# MEMORY.net
KiCad netlist of a schematic drawn in Altium Designer
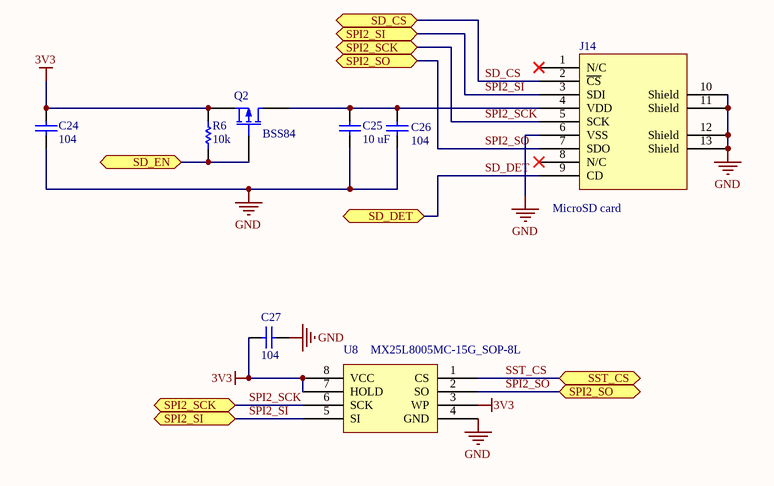
[diagram p0: MEMORY.SchDoc]

(export (version "E")
  (design (tool "Eeschema 10.0.6"))
  (components
    (comp (ref "C24")
      (value "104")
      (footprint "C0603")
      (description "CAP CER 0.1UF 16V Y5V 0402")
      (fields
        (field (name "MANUFACTURER") "Yageo")
        (field (name "DIGI-KEY PART NUMBER") "311-1047-1-ND")
        (field (name "PUBLISHER") "Altium Limited")
      )
      (libsource (lib "RobotClub") (part "Cap_SMT"))
    )
    (comp (ref "C25")
      (value "10 uF")
      (footprint "C1210")
      (description "CAP CER 0.1UF 16V Y5V 0402")
      (fields
        (field (name "MANUFACTURER") "Yageo")
        (field (name "DIGI-KEY PART NUMBER") "311-1047-1-ND")
        (field (name "PUBLISHER") "Altium Limited")
      )
      (libsource (lib "RobotClub") (part "Cap_SMT"))
    )
    (comp (ref "C26")
      (value "104")
      (footprint "C0603")
      (description "CAP CER 0.1UF 16V Y5V 0402")
      (fields
        (field (name "MANUFACTURER") "Yageo")
        (field (name "DIGI-KEY PART NUMBER") "311-1047-1-ND")
        (field (name "PUBLISHER") "Altium Limited")
      )
      (libsource (lib "RobotClub") (part "Cap_SMT"))
    )
    (comp (ref "C27")
      (value "104")
      (footprint "C0603")
      (description "CAP CER 0.1UF 16V Y5V 0402")
      (fields
        (field (name "MANUFACTURER") "Yageo")
        (field (name "DIGI-KEY PART NUMBER") "311-1047-1-ND")
        (field (name "PUBLISHER") "Altium Limited")
      )
      (libsource (lib "RobotClub") (part "Cap_SMT"))
    )
    (comp (ref "J14")
      (value "MicroSD card")
      (footprint "MICROSD SOCKET CPSDBT5")
      (fields (field (name "DIGI-KEY PART NUMBER") "NA"))
      (libsource (lib "uSD push-push socket") (part "uSD Push-Push Socket"))
    )
    (comp (ref "Q2")
      (value "BSS84")
      (footprint "SOT23-3")
      (description "MOSFET P-CH 50V 130MA SOT23-3")
      (fields
        (field (name "DIGI-KEY PART NUMBER") "BSS84-FDITR-ND")
        (field (name "MANUFACTURER") "Diodes Inc")
        (field (name "PUBLISHER") "Altium Limited")
      )
      (libsource (lib "RobotClub") (part "MOSFET-P GSD"))
    )
    (comp (ref "R6")
      (value "10k")
      (footprint "R0603")
      (description "Resistor SMD 5%")
      (fields
        (field (name "DIGI-KEY PART NUMBER") "P3.24KLTR-ND")
        (field (name "MANUFACTURER") "Panasonic Electronic Components")
        (field (name "PUBLISHER") "Altium Limited")
      )
      (libsource (lib "RobotClub") (part "R_SMD5"))
    )
    (comp (ref "U8")
      (value "MX25L8005MC-15G_SOP-8L")
      (footprint "FLASH_IC")
      (fields (field (name "DIGI-KEY PART NUMBER") "1092-1106-ND"))
      (libsource (lib "GT402Dlib") (part "MX25L8005MC-15G_SOP-8L"))
    )
  )
  (nets
    (net (code "1") (name "/SD_CS") (class "Default")
      (node (ref "J14") (pin "2") (pinfunction "~{CS}_2") (pintype "passive"))
    )
    (net (code "2") (name "/SD_DET") (class "Default")
      (node (ref "J14") (pin "9") (pinfunction "CD_9") (pintype "passive"))
    )
    (net (code "3") (name "/SD_EN") (class "Default")
      (node (ref "Q2") (pin "1") (pinfunction "G_1") (pintype "passive"))
      (node (ref "R6") (pin "2") (pinfunction "2_2") (pintype "passive"))
    )
    (net (code "4") (name "/SPI2_SCK") (class "Default")
      (node (ref "J14") (pin "5") (pinfunction "SCK_5") (pintype "passive"))
      (node (ref "U8") (pin "6") (pinfunction "SCK_6") (pintype "passive"))
    )
    (net (code "5") (name "/SPI2_SI") (class "Default")
      (node (ref "J14") (pin "3") (pinfunction "SDI_3") (pintype "passive"))
      (node (ref "U8") (pin "5") (pinfunction "SI_5") (pintype "passive"))
    )
    (net (code "6") (name "/SPI2_SO") (class "Default")
      (node (ref "J14") (pin "7") (pinfunction "SDO_7") (pintype "passive"))
      (node (ref "U8") (pin "2") (pinfunction "SO_2") (pintype "passive"))
    )
    (net (code "7") (name "/SST_CS") (class "Default")
      (node (ref "U8") (pin "1") (pinfunction "CS_1") (pintype "passive"))
    )
    (net (code "8") (name "3V3") (class "Default")
      (node (ref "C24") (pin "2") (pinfunction "2_2") (pintype "passive"))
      (node (ref "C27") (pin "2") (pinfunction "2_2") (pintype "passive"))
      (node (ref "Q2") (pin "2") (pinfunction "S_2") (pintype "passive"))
      (node (ref "R6") (pin "1") (pinfunction "1_1") (pintype "passive"))
      (node (ref "U8") (pin "3") (pinfunction "WP_3") (pintype "passive"))
      (node (ref "U8") (pin "7") (pinfunction "HOLD_7") (pintype "passive"))
      (node (ref "U8") (pin "8") (pinfunction "VCC_8") (pintype "passive"))
    )
    (net (code "9") (name "GND") (class "Default")
      (node (ref "C24") (pin "1") (pinfunction "1_1") (pintype "passive"))
      (node (ref "C25") (pin "1") (pinfunction "1_1") (pintype "passive"))
      (node (ref "C26") (pin "1") (pinfunction "1_1") (pintype "passive"))
      (node (ref "C27") (pin "1") (pinfunction "1_1") (pintype "passive"))
      (node (ref "J14") (pin "10") (pinfunction "Shield_10") (pintype "passive"))
      (node (ref "J14") (pin "11") (pinfunction "Shield_11") (pintype "passive"))
      (node (ref "J14") (pin "12") (pinfunction "Shield_12") (pintype "passive"))
      (node (ref "J14") (pin "13") (pinfunction "Shield_13") (pintype "passive"))
      (node (ref "J14") (pin "6") (pinfunction "VSS_6") (pintype "passive"))
      (node (ref "U8") (pin "4") (pinfunction "GND_4") (pintype "passive"))
    )
    (net (code "10") (name "Net-(J14-VDD)") (class "Default")
      (node (ref "C25") (pin "2") (pinfunction "2_2") (pintype "passive"))
      (node (ref "C26") (pin "2") (pinfunction "2_2") (pintype "passive"))
      (node (ref "J14") (pin "4") (pinfunction "VDD_4") (pintype "passive"))
      (node (ref "Q2") (pin "3") (pinfunction "D_3") (pintype "passive"))
    )
    (net (code "11") (name "unconnected-(J14-N{slash}C-Pad1)") (class "Default")
      (node (ref "J14") (pin "1") (pinfunction "N/C_1") (pintype "passive+no_connect"))
    )
    (net (code "12") (name "unconnected-(J14-N{slash}C-Pad8)") (class "Default")
      (node (ref "J14") (pin "8") (pinfunction "N/C_8") (pintype "passive+no_connect"))
    )
  )
)
